# preamp_transistor.net
KiCad netlist of a schematic drawn in EasyEDA
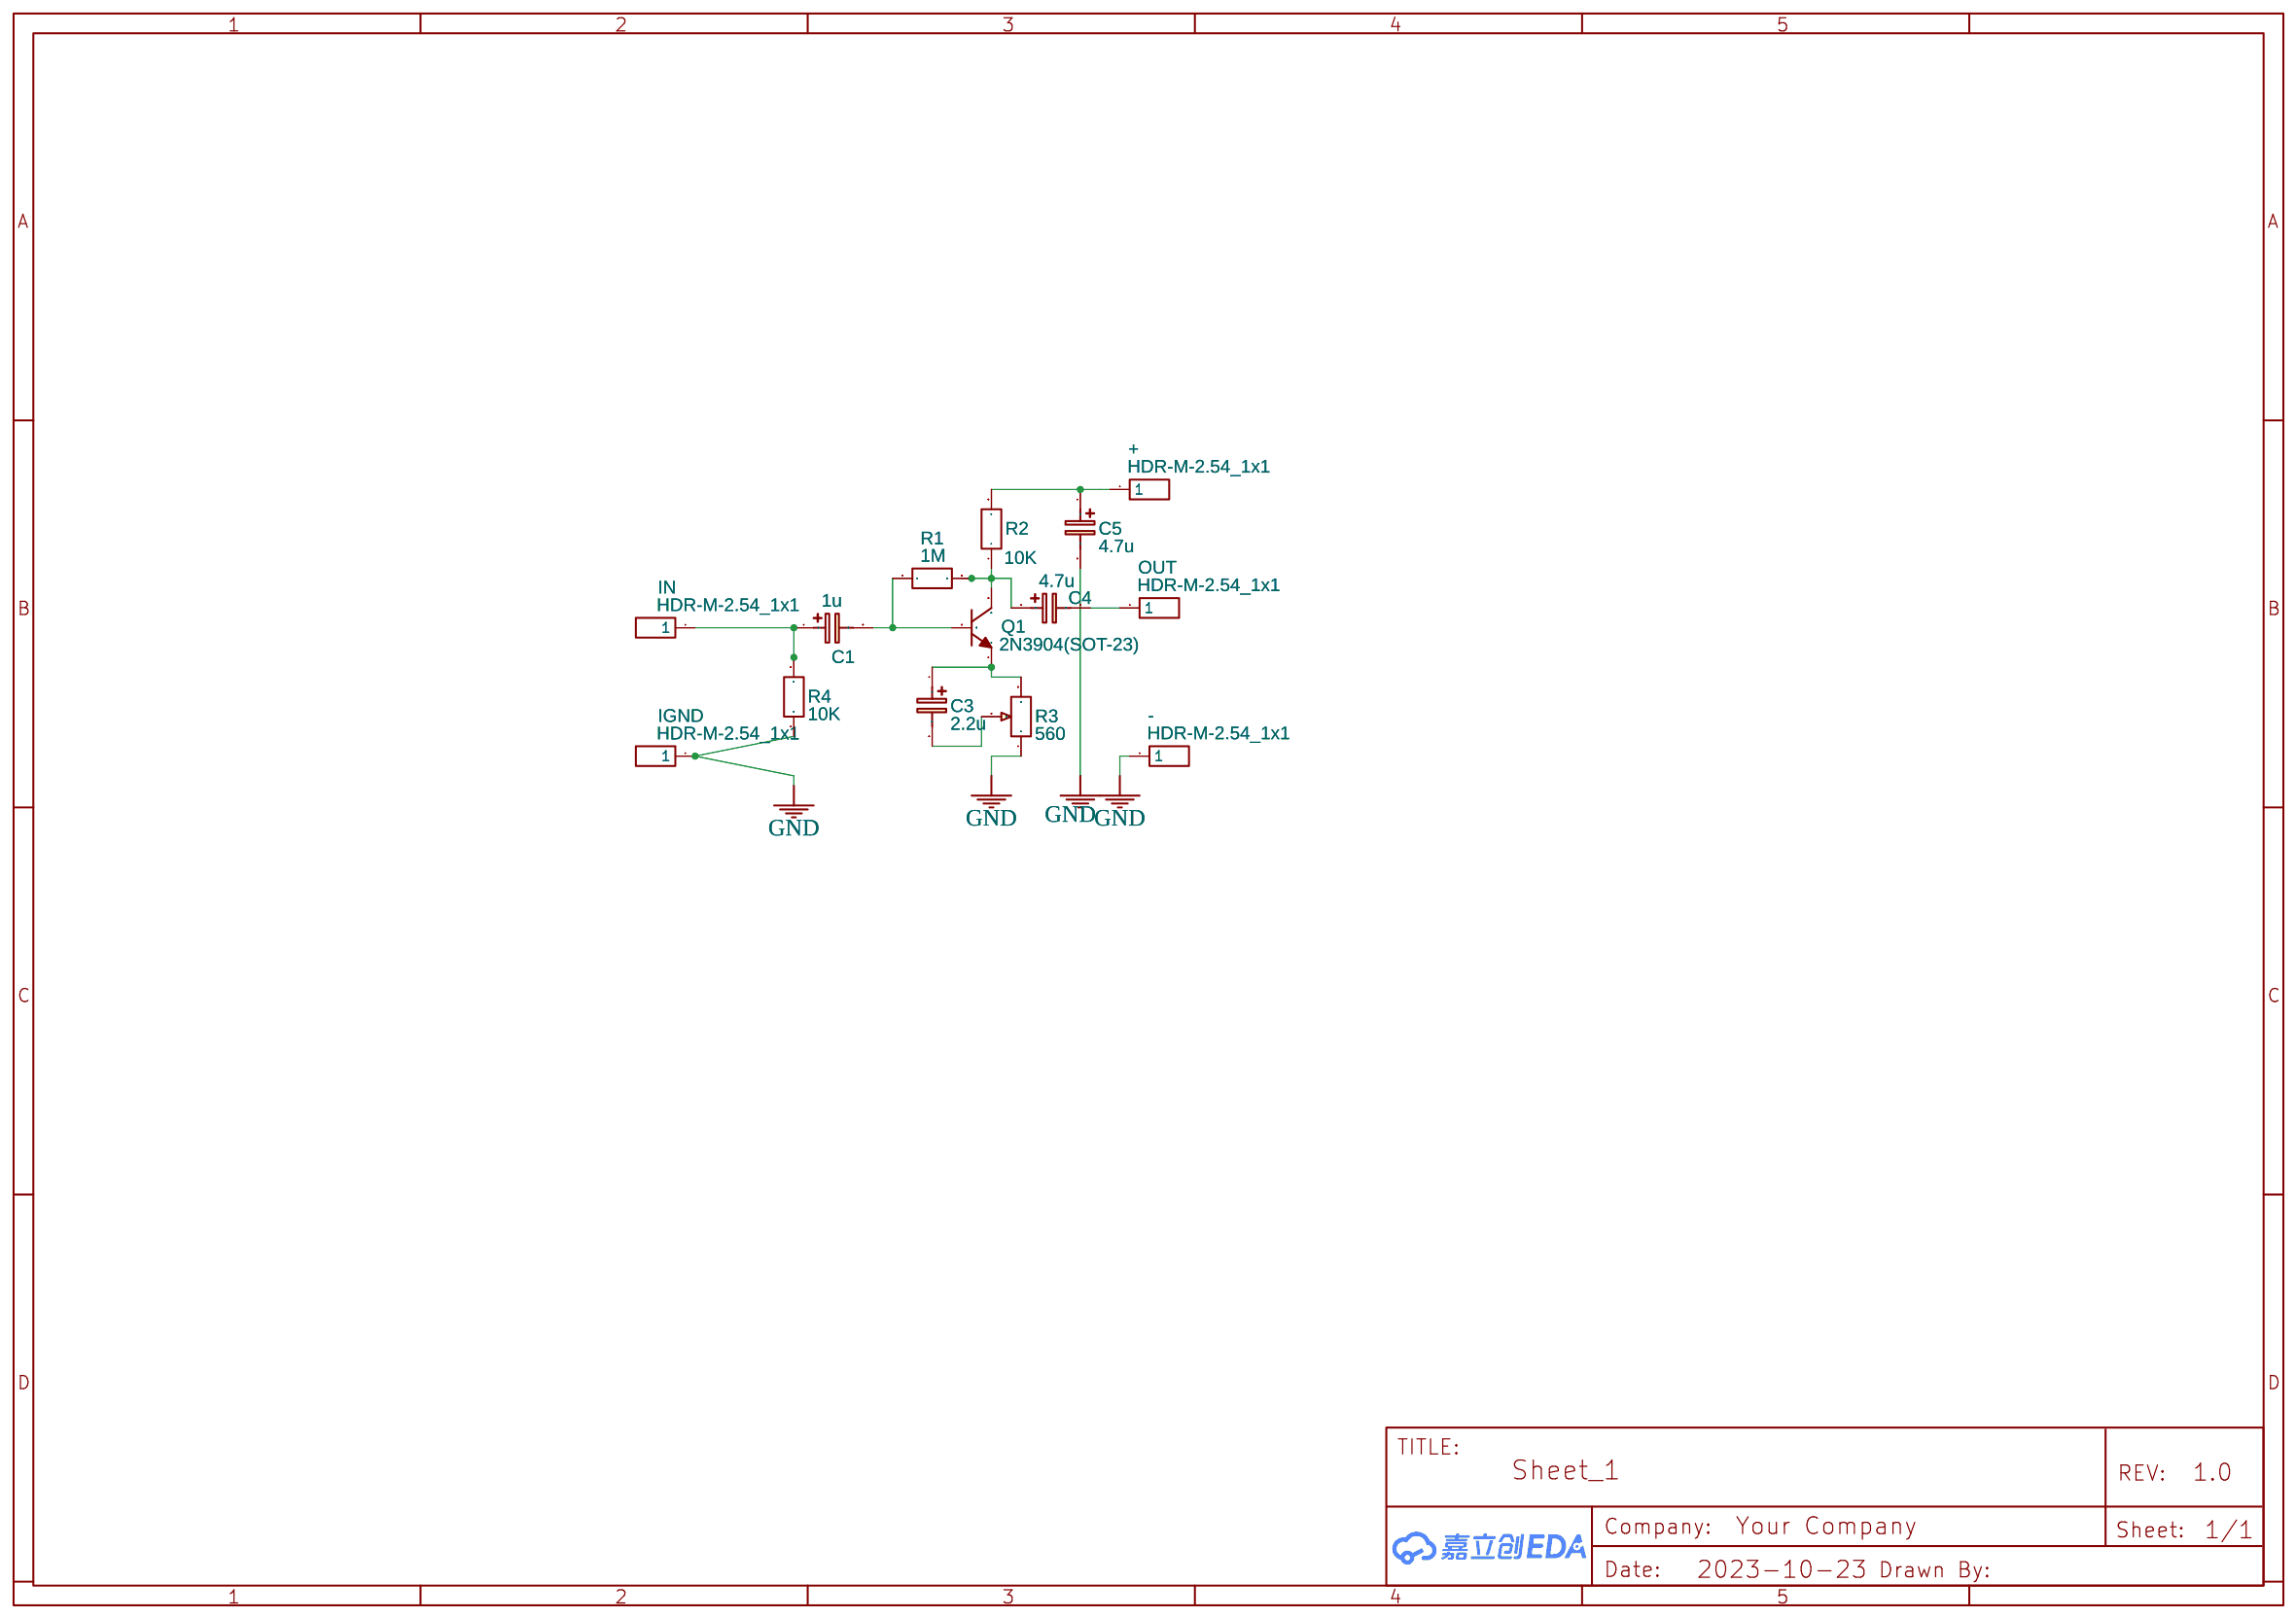
[diagram p0: schematic sheet]

(export (version "E")
  (design (tool "Eeschema 10.0.6"))
  (components
    (comp (ref "+")
      (value "HDR-M-2.54_1x1")
      (fields (field (name "BOM_Supplier Part") "C81276"))
      (libsource (lib "") (part "HDR-M-2.54_1x1_4"))
    )
    (comp (ref "-")
      (value "HDR-M-2.54_1x1")
      (fields (field (name "BOM_Supplier Part") "C81276"))
      (libsource (lib "") (part "HDR-M-2.54_1x1_1"))
    )
    (comp (ref "C1") (value "1u") (libsource (lib "") (part "C_Tan_SMD_A_EU_1")))
    (comp (ref "C3") (value "2.2u") (libsource (lib "") (part "C_Tan_SMD_A_EU")))
    (comp (ref "C4") (value "4.7u") (libsource (lib "") (part "C_Tan_SMD_A_EU_3")))
    (comp (ref "C5") (value "4.7u") (libsource (lib "") (part "C_Tan_SMD_A_EU_2")))
    (comp (ref "IGND")
      (value "HDR-M-2.54_1x1")
      (fields (field (name "BOM_Supplier Part") "C81276"))
      (libsource (lib "") (part "HDR-M-2.54_1x1_3"))
    )
    (comp (ref "IN")
      (value "HDR-M-2.54_1x1")
      (fields (field (name "BOM_Supplier Part") "C81276"))
      (libsource (lib "") (part "HDR-M-2.54_1x1_2"))
    )
    (comp (ref "OUT")
      (value "HDR-M-2.54_1x1")
      (fields (field (name "BOM_Supplier Part") "C81276"))
      (libsource (lib "") (part "HDR-M-2.54_1x1"))
    )
    (comp (ref "Q1")
      (value "2N3904(SOT-23)")
      (fields
        (field (name "BOM_Manufacturer Part") "2n3904S-RTK/PS")
        (field (name "BOM_Supplier Part") "C18536")
      )
      (libsource (lib "") (part "2N3904(SOT-23)"))
    )
    (comp (ref "R1") (value "1M") (libsource (lib "") (part "R_0603_EU")))
    (comp (ref "R2") (value "10K") (libsource (lib "") (part "R_0603_EU_1")))
    (comp (ref "R3")
      (value "560")
      (fields (field (name "Manufacturer Part") "RM063-103 10K") (field (name "Manufacturer") "JML"))
      (libsource (lib "") (part "RM063-103 10K"))
    )
    (comp (ref "R4") (value "10K") (libsource (lib "") (part "R_0603_EU_1")))
  )
  (nets
    (net (code "1") (name "GND") (class "Default")
      (node (ref "-") (pin "1") (pinfunction "1_1") (pintype "input"))
      (node (ref "C5") (pin "2") (pinfunction "2_2") (pintype "unspecified"))
      (node (ref "IGND") (pin "1") (pinfunction "1_1") (pintype "input"))
      (node (ref "R3") (pin "1") (pinfunction "1_1") (pintype "input"))
      (node (ref "R4") (pin "1") (pinfunction "1_1") (pintype "unspecified"))
    )
    (net (code "2") (name "Net-(+-Pad1)") (class "Default")
      (node (ref "+") (pin "1") (pinfunction "1_1") (pintype "input"))
      (node (ref "C5") (pin "1") (pinfunction "1_1") (pintype "unspecified"))
      (node (ref "R2") (pin "2") (pinfunction "2_2") (pintype "unspecified"))
    )
    (net (code "3") (name "Net-(C1-Pad1)") (class "Default")
      (node (ref "C1") (pin "1") (pinfunction "1_1") (pintype "unspecified"))
      (node (ref "IN") (pin "1") (pinfunction "1_1") (pintype "input"))
      (node (ref "R4") (pin "2") (pinfunction "2_2") (pintype "unspecified"))
    )
    (net (code "4") (name "Net-(C3-Pad2)") (class "Default")
      (node (ref "C3") (pin "2") (pinfunction "2_2") (pintype "unspecified"))
      (node (ref "R3") (pin "2") (pinfunction "2_2") (pintype "input"))
    )
    (net (code "5") (name "Net-(C4-Pad2)") (class "Default")
      (node (ref "C4") (pin "2") (pinfunction "2_2") (pintype "unspecified"))
      (node (ref "OUT") (pin "1") (pinfunction "1_1") (pintype "input"))
    )
    (net (code "6") (name "Net-(Q1-B)") (class "Default")
      (node (ref "C1") (pin "2") (pinfunction "2_2") (pintype "unspecified"))
      (node (ref "Q1") (pin "2") (pinfunction "B_2") (pintype "input"))
      (node (ref "R1") (pin "1") (pinfunction "1_1") (pintype "unspecified"))
    )
    (net (code "7") (name "Net-(Q1-C)") (class "Default")
      (node (ref "C4") (pin "1") (pinfunction "1_1") (pintype "unspecified"))
      (node (ref "Q1") (pin "3") (pinfunction "C_3") (pintype "input"))
      (node (ref "R1") (pin "2") (pinfunction "2_2") (pintype "unspecified"))
      (node (ref "R2") (pin "1") (pinfunction "1_1") (pintype "unspecified"))
    )
    (net (code "8") (name "Net-(Q1-E)") (class "Default")
      (node (ref "C3") (pin "1") (pinfunction "1_1") (pintype "unspecified"))
      (node (ref "Q1") (pin "1") (pinfunction "E_1") (pintype "input"))
      (node (ref "R3") (pin "3") (pinfunction "3_3") (pintype "input"))
    )
  )
)
